# main_board.net
KiCad netlist of a schematic drawn in EAGLE
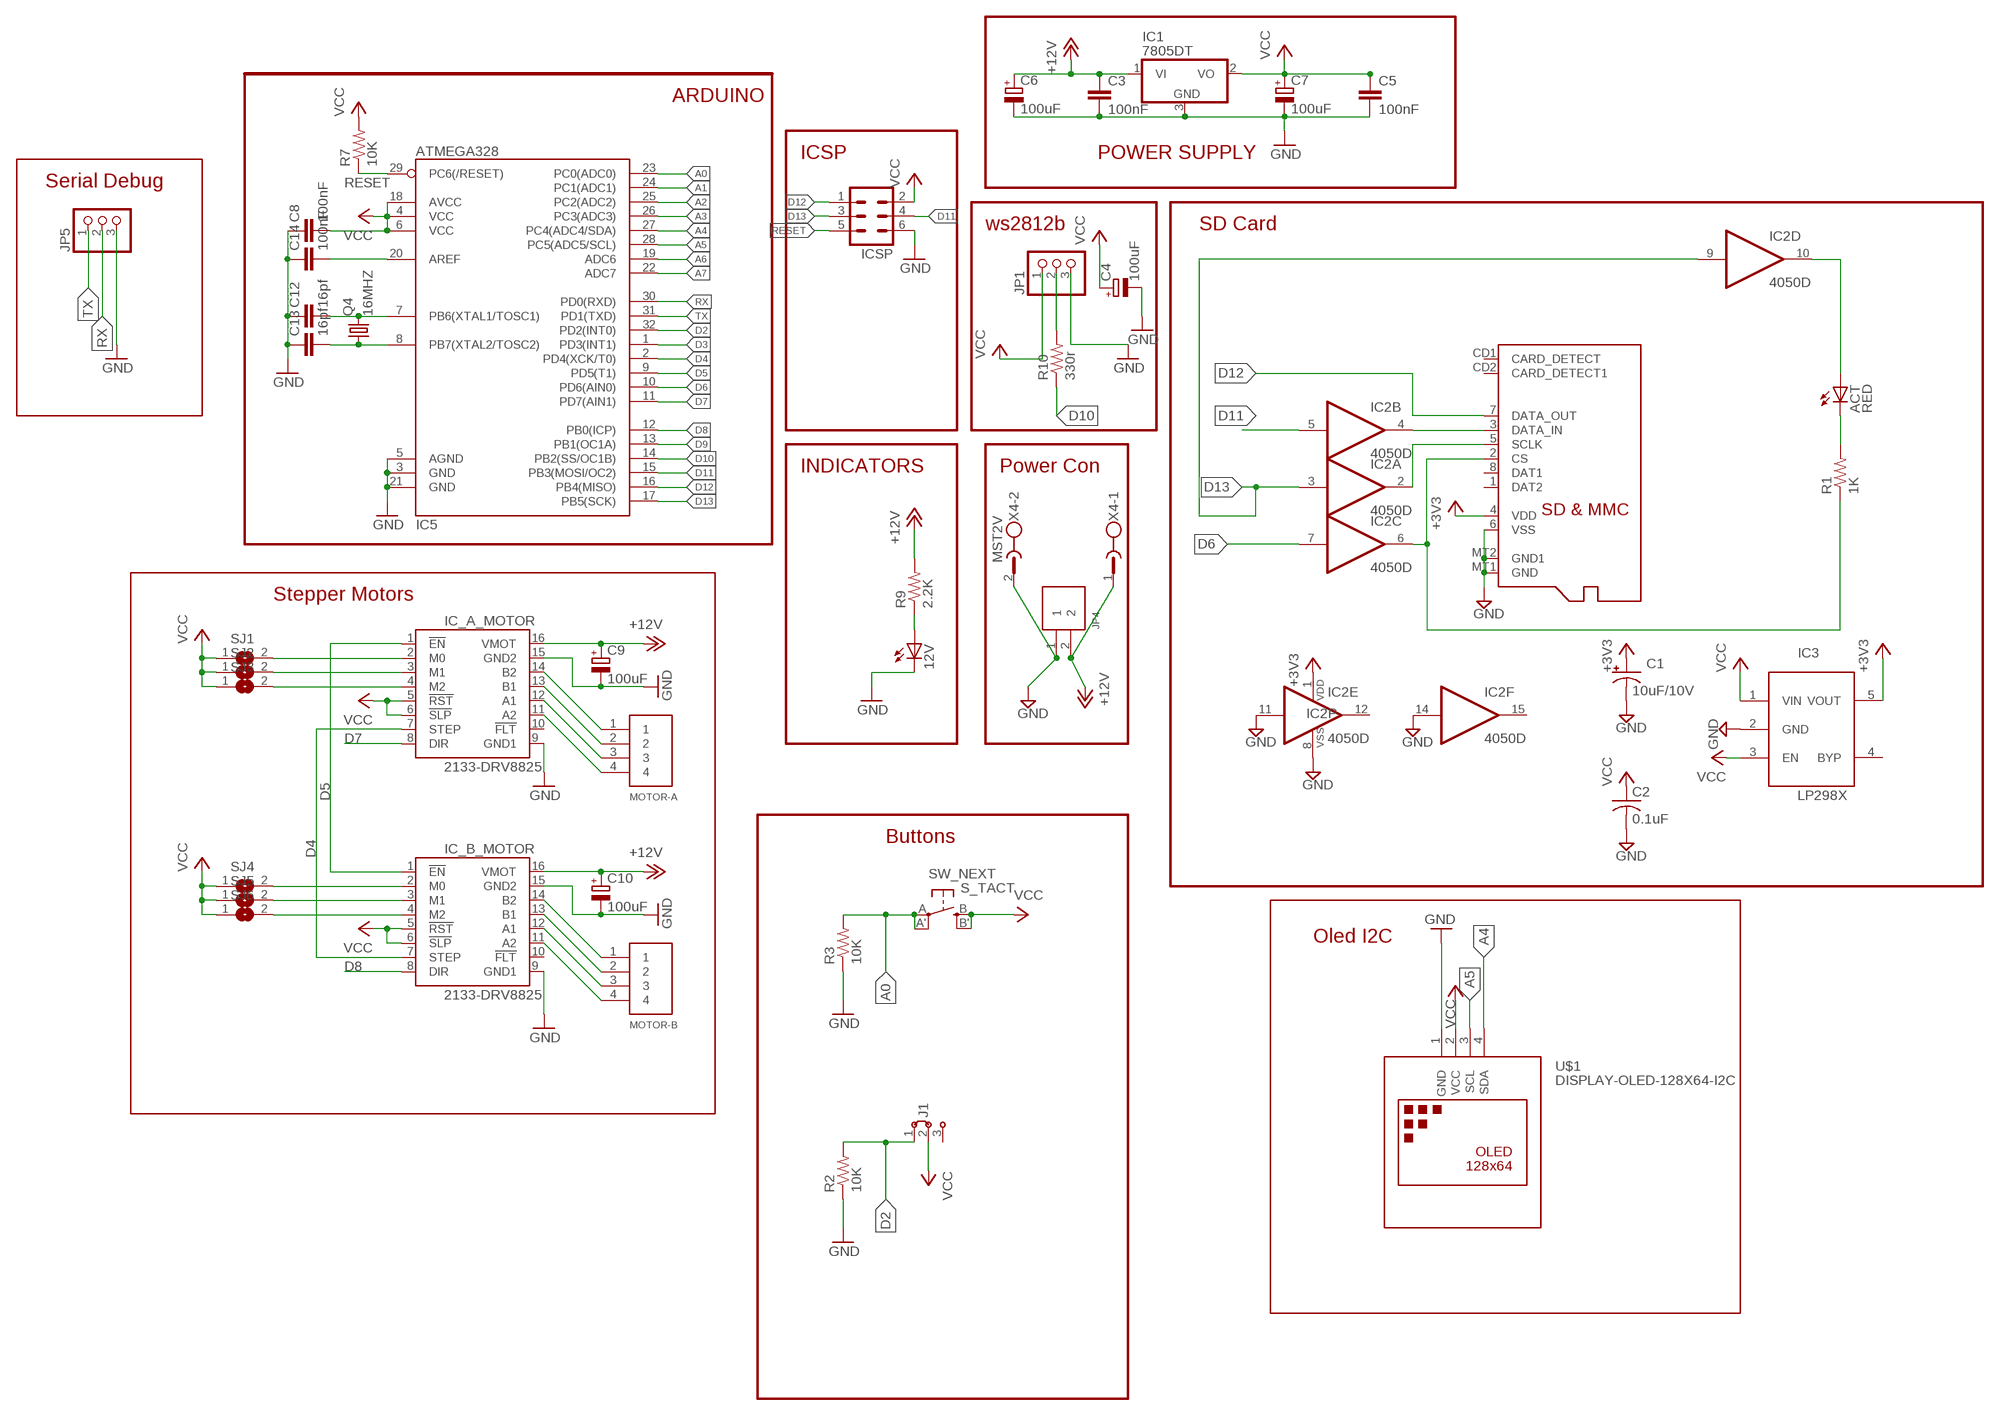
[diagram p0: schematic, sheet 1]

(export (version "E")
  (design (tool "Eeschema 10.0.6"))
  (components
    (comp (ref "12V")
      (value "LED0805")
      (footprint "eagle-import:LED-0805")
      (libsource (lib "eagle-import") (part "LED0805"))
    )
    (comp (ref "ACT")
      (value "RED")
      (footprint "eagle-import:CHIP-LED0805")
      (libsource (lib "eagle-import") (part "LEDCHIP-LED0805"))
    )
    (comp (ref "C1")
      (value "10uF/10V")
      (footprint "eagle-import:A_3216-18R")
      (libsource (lib "eagle-import") (part "CPOL-USA/3216-18R"))
    )
    (comp (ref "C2")
      (value "0.1uF")
      (footprint "eagle-import:C0805K")
      (libsource (lib "eagle-import") (part "C-USC0805K"))
    )
    (comp (ref "C3")
      (value "100nF")
      (footprint "eagle-import:0805")
      (libsource (lib "eagle-import") (part "CAP0805"))
    )
    (comp (ref "C4")
      (value "100uF")
      (footprint "eagle-import:E3,5-8")
      (libsource (lib "eagle-import") (part "CPOL-EUE3.5-8"))
    )
    (comp (ref "C5")
      (value "100nF")
      (footprint "eagle-import:0805")
      (libsource (lib "eagle-import") (part "CAP0805"))
    )
    (comp (ref "C6")
      (value "100uF")
      (footprint "eagle-import:E3,5-8")
      (libsource (lib "eagle-import") (part "CPOL-EUE3.5-8"))
    )
    (comp (ref "C7")
      (value "100uF")
      (footprint "eagle-import:E3,5-8")
      (libsource (lib "eagle-import") (part "CPOL-EUE3.5-8"))
    )
    (comp (ref "C8")
      (value "100nF")
      (footprint "eagle-import:0805")
      (libsource (lib "eagle-import") (part "CAP0805"))
    )
    (comp (ref "C9")
      (value "100uF")
      (footprint "eagle-import:E3,5-8")
      (libsource (lib "eagle-import") (part "CPOL-EUE3.5-8"))
    )
    (comp (ref "C10")
      (value "100uF")
      (footprint "eagle-import:E3,5-8")
      (libsource (lib "eagle-import") (part "CPOL-EUE3.5-8"))
    )
    (comp (ref "C12")
      (value "16pf")
      (footprint "eagle-import:0805")
      (libsource (lib "eagle-import") (part "CAP0805"))
    )
    (comp (ref "C13")
      (value "16pf")
      (footprint "eagle-import:0805")
      (libsource (lib "eagle-import") (part "CAP0805"))
    )
    (comp (ref "C14")
      (value "100nF")
      (footprint "eagle-import:0805")
      (libsource (lib "eagle-import") (part "CAP0805"))
    )
    (comp (ref "IC1")
      (value "7805DT")
      (footprint "eagle-import:TO252")
      (libsource (lib "eagle-import") (part "78DT05"))
    )
    (comp (ref "IC2")
      (value "4050D")
      (footprint "eagle-import:SO16")
      (libsource (lib "eagle-import") (part "4050D"))
    )
    (comp (ref "IC3")
      (value "LP298XS")
      (footprint "eagle-import:SOT23-5L")
      (libsource (lib "eagle-import") (part "LP298XS"))
    )
    (comp (ref "IC5")
      (value "ATMEGA328")
      (footprint "eagle-import:TQFP32-08")
      (libsource (lib "eagle-import") (part "ATMEGA168"))
    )
    (comp (ref "ICSP")
      (value "ML6")
      (footprint "eagle-import:ML6")
      (libsource (lib "eagle-import") (part "ML6"))
    )
    (comp (ref "IC_A_MOTOR")
      (value "2133-DRV8825")
      (footprint "eagle-import:DRV8825")
      (libsource (lib "eagle-import") (part "2133-DRV8825"))
    )
    (comp (ref "IC_B_MOTOR")
      (value "2133-DRV8825")
      (footprint "eagle-import:DRV8825")
      (libsource (lib "eagle-import") (part "2133-DRV8825"))
    )
    (comp (ref "J1")
      (value "J2X5MM")
      (footprint "eagle-import:05C")
      (libsource (lib "eagle-import") (part "J2X5MM"))
    )
    (comp (ref "JP1")
      (value "PINHD-1X3")
      (footprint "eagle-import:1X03")
      (libsource (lib "eagle-import") (part "PINHD-1X3"))
    )
    (comp (ref "JP4")
      (value "2PIN")
      (footprint "eagle-import:B2B-PH-K-S")
      (libsource (lib "eagle-import") (part "2PIN"))
    )
    (comp (ref "JP5")
      (value "PINHD-1X3")
      (footprint "eagle-import:1X03")
      (libsource (lib "eagle-import") (part "PINHD-1X3"))
    )
    (comp (ref "MOTOR-A")
      (value "4PIN")
      (footprint "eagle-import:B4B-PH-K-S")
      (libsource (lib "eagle-import") (part "4PIN"))
    )
    (comp (ref "MOTOR-B")
      (value "4PIN")
      (footprint "eagle-import:B4B-PH-K-S")
      (libsource (lib "eagle-import") (part "4PIN"))
    )
    (comp (ref "Q4")
      (value "16MHZ")
      (footprint "eagle-import:HC49_S")
      (libsource (lib "eagle-import") (part "CRYSTALHC49S"))
    )
    (comp (ref "R1")
      (value "1K")
      (footprint "eagle-import:R0805")
      (libsource (lib "eagle-import") (part "R-US_R0805"))
    )
    (comp (ref "R2")
      (value "10K")
      (footprint "eagle-import:R0805")
      (libsource (lib "eagle-import") (part "R-US_R0805"))
    )
    (comp (ref "R3")
      (value "10K")
      (footprint "eagle-import:R0805")
      (libsource (lib "eagle-import") (part "R-US_R0805"))
    )
    (comp (ref "R7")
      (value "10K")
      (footprint "eagle-import:0805")
      (libsource (lib "eagle-import") (part "RESISTOR"))
    )
    (comp (ref "R9")
      (value "2.2K")
      (footprint "eagle-import:0805")
      (libsource (lib "eagle-import") (part "RESISTOR"))
    )
    (comp (ref "R10")
      (value "330r")
      (footprint "eagle-import:R0805")
      (libsource (lib "eagle-import") (part "R-US_R0805"))
    )
    (comp (ref "SJ1") (value "SJ") (footprint "eagle-import:SJ") (libsource (lib "eagle-import") (part "SJ")))
    (comp (ref "SJ2") (value "SJ") (footprint "eagle-import:SJ") (libsource (lib "eagle-import") (part "SJ")))
    (comp (ref "SJ3") (value "SJ") (footprint "eagle-import:SJ") (libsource (lib "eagle-import") (part "SJ")))
    (comp (ref "SJ4") (value "SJ") (footprint "eagle-import:SJ") (libsource (lib "eagle-import") (part "SJ")))
    (comp (ref "SJ5") (value "SJ") (footprint "eagle-import:SJ") (libsource (lib "eagle-import") (part "SJ")))
    (comp (ref "SJ6") (value "SJ") (footprint "eagle-import:SJ") (libsource (lib "eagle-import") (part "SJ")))
    (comp (ref "SW_NEXT")
      (value "S_TACT")
      (footprint "eagle-import:EVQ-Q2")
      (libsource (lib "eagle-import") (part "SPST_TACT-EVQQ2"))
    )
    (comp (ref "U$1")
      (value "DISPLAY-OLED-128X64-I2C")
      (footprint "eagle-import:DISPLAY-OLED-128X64-I2C")
      (libsource (lib "eagle-import") (part "DISPLAY-OLED-128X64-I2C"))
    )
    (comp (ref "X1")
      (value "MICROSD")
      (footprint "eagle-import:MICROSD")
      (libsource (lib "eagle-import") (part "MICROSD"))
    )
    (comp (ref "X4")
      (value "MST2V")
      (footprint "eagle-import:MSTBV2")
      (libsource (lib "eagle-import") (part "MST2V"))
    )
  )
  (nets
    (net (code "1") (name "+3V3") (class "Default")
      (node (ref "C1") (pin "+") (pinfunction "+_+") (pintype "passive"))
      (node (ref "IC2") (pin "1") (pinfunction "VDD_1") (pintype "power_in"))
      (node (ref "IC3") (pin "5") (pinfunction "VOUT_5") (pintype "bidirectional"))
      (node (ref "X1") (pin "4") (pinfunction "VDD_4") (pintype "power_in"))
    )
    (net (code "2") (name "+12V") (class "Default")
      (node (ref "C10") (pin "+") (pinfunction "+_+") (pintype "passive"))
      (node (ref "C3") (pin "1") (pinfunction "1_1") (pintype "passive"))
      (node (ref "C6") (pin "+") (pinfunction "+_+") (pintype "passive"))
      (node (ref "C9") (pin "+") (pinfunction "+_+") (pintype "passive"))
      (node (ref "IC1") (pin "1") (pinfunction "VI_1") (pintype "input"))
      (node (ref "IC_A_MOTOR") (pin "16") (pinfunction "VMOT_16") (pintype "power_in"))
      (node (ref "IC_B_MOTOR") (pin "16") (pinfunction "VMOT_16") (pintype "power_in"))
      (node (ref "JP4") (pin "2") (pinfunction "2_2") (pintype "bidirectional"))
      (node (ref "R9") (pin "2") (pinfunction "2_2") (pintype "passive"))
      (node (ref "X4") (pin "1") (pinfunction "1_1") (pintype "passive"))
    )
    (net (code "3") (name "A0") (class "Default")
      (node (ref "IC5") (pin "23") (pinfunction "PC0(ADC0)_23") (pintype "bidirectional"))
      (node (ref "R3") (pin "2") (pinfunction "2_2") (pintype "passive"))
      (node (ref "SW_NEXT") (pin "A") (pinfunction "P_A") (pintype "passive"))
      (node (ref "SW_NEXT") (pin "A'") (pinfunction "P1_A'") (pintype "passive"))
    )
    (net (code "4") (name "A1") (class "Default")
      (node (ref "IC5") (pin "24") (pinfunction "PC1(ADC1)_24") (pintype "bidirectional"))
    )
    (net (code "5") (name "A2") (class "Default")
      (node (ref "IC5") (pin "25") (pinfunction "PC2(ADC2)_25") (pintype "bidirectional"))
    )
    (net (code "6") (name "A3") (class "Default")
      (node (ref "IC5") (pin "26") (pinfunction "PC3(ADC3)_26") (pintype "bidirectional"))
    )
    (net (code "7") (name "A4") (class "Default")
      (node (ref "IC5") (pin "27") (pinfunction "PC4(ADC4/SDA)_27") (pintype "bidirectional"))
      (node (ref "U$1") (pin "4") (pinfunction "SDA_4") (pintype "bidirectional"))
    )
    (net (code "8") (name "A5") (class "Default")
      (node (ref "IC5") (pin "28") (pinfunction "PC5(ADC5/SCL)_28") (pintype "bidirectional"))
      (node (ref "U$1") (pin "3") (pinfunction "SCL_3") (pintype "bidirectional"))
    )
    (net (code "9") (name "A6") (class "Default")
      (node (ref "IC5") (pin "19") (pinfunction "ADC6_19") (pintype "bidirectional"))
    )
    (net (code "10") (name "A7") (class "Default")
      (node (ref "IC5") (pin "22") (pinfunction "ADC7_22") (pintype "bidirectional"))
    )
    (net (code "11") (name "D2") (class "Default")
      (node (ref "IC5") (pin "32") (pinfunction "PD2(INT0)_32") (pintype "bidirectional"))
      (node (ref "J1") (pin "1") (pinfunction "1_1") (pintype "passive"))
      (node (ref "R2") (pin "2") (pinfunction "2_2") (pintype "passive"))
    )
    (net (code "12") (name "D3") (class "Default")
      (node (ref "IC5") (pin "1") (pinfunction "PD3(INT1)_1") (pintype "bidirectional"))
    )
    (net (code "13") (name "D4") (class "Default")
      (node (ref "IC5") (pin "2") (pinfunction "PD4(XCK/T0)_2") (pintype "bidirectional"))
      (node (ref "IC_A_MOTOR") (pin "7") (pinfunction "STEP_7") (pintype "input"))
      (node (ref "IC_B_MOTOR") (pin "7") (pinfunction "STEP_7") (pintype "input"))
    )
    (net (code "14") (name "D5") (class "Default")
      (node (ref "IC5") (pin "9") (pinfunction "PD5(T1)_9") (pintype "bidirectional"))
      (node (ref "IC_A_MOTOR") (pin "1") (pinfunction "~{EN}_1") (pintype "passive"))
      (node (ref "IC_B_MOTOR") (pin "1") (pinfunction "~{EN}_1") (pintype "passive"))
    )
    (net (code "15") (name "D6") (class "Default")
      (node (ref "IC2") (pin "7") (pinfunction "I_7") (pintype "input"))
      (node (ref "IC5") (pin "10") (pinfunction "PD6(AIN0)_10") (pintype "bidirectional"))
    )
    (net (code "16") (name "D7") (class "Default")
      (node (ref "IC5") (pin "11") (pinfunction "PD7(AIN1)_11") (pintype "bidirectional"))
      (node (ref "IC_A_MOTOR") (pin "8") (pinfunction "DIR_8") (pintype "input"))
    )
    (net (code "17") (name "D8") (class "Default")
      (node (ref "IC5") (pin "12") (pinfunction "PB0(ICP)_12") (pintype "bidirectional"))
      (node (ref "IC_B_MOTOR") (pin "8") (pinfunction "DIR_8") (pintype "input"))
    )
    (net (code "18") (name "D9") (class "Default")
      (node (ref "IC5") (pin "13") (pinfunction "PB1(OC1A)_13") (pintype "bidirectional"))
    )
    (net (code "19") (name "D10") (class "Default")
      (node (ref "IC5") (pin "14") (pinfunction "PB2(SS/OC1B)_14") (pintype "bidirectional"))
      (node (ref "R10") (pin "1") (pinfunction "1_1") (pintype "passive"))
    )
    (net (code "20") (name "D11") (class "Default")
      (node (ref "IC2") (pin "5") (pinfunction "I_5") (pintype "input"))
      (node (ref "IC5") (pin "15") (pinfunction "PB3(MOSI/OC2)_15") (pintype "bidirectional"))
      (node (ref "ICSP") (pin "4") (pinfunction "4_4") (pintype "passive"))
    )
    (net (code "21") (name "D12") (class "Default")
      (node (ref "IC5") (pin "16") (pinfunction "PB4(MISO)_16") (pintype "bidirectional"))
      (node (ref "ICSP") (pin "1") (pinfunction "1_1") (pintype "passive"))
      (node (ref "X1") (pin "7") (pinfunction "DATA_OUT_7") (pintype "output"))
    )
    (net (code "22") (name "D13") (class "Default")
      (node (ref "IC2") (pin "3") (pinfunction "I_3") (pintype "input"))
      (node (ref "IC2") (pin "9") (pinfunction "I_9") (pintype "input"))
      (node (ref "IC5") (pin "17") (pinfunction "PB5(SCK)_17") (pintype "bidirectional"))
      (node (ref "ICSP") (pin "3") (pinfunction "3_3") (pintype "passive"))
    )
    (net (code "23") (name "GND") (class "Default")
      (node (ref "12V") (pin "C") (pinfunction "C_C") (pintype "passive"))
      (node (ref "C1") (pin "-") (pinfunction "-_-") (pintype "passive"))
      (node (ref "C10") (pin "-") (pinfunction "-_-") (pintype "passive"))
      (node (ref "C12") (pin "1") (pinfunction "1_1") (pintype "passive"))
      (node (ref "C13") (pin "1") (pinfunction "1_1") (pintype "passive"))
      (node (ref "C14") (pin "1") (pinfunction "1_1") (pintype "passive"))
      (node (ref "C2") (pin "2") (pinfunction "2_2") (pintype "passive"))
      (node (ref "C3") (pin "2") (pinfunction "2_2") (pintype "passive"))
      (node (ref "C4") (pin "-") (pinfunction "-_-") (pintype "passive"))
      (node (ref "C5") (pin "2") (pinfunction "2_2") (pintype "passive"))
      (node (ref "C6") (pin "-") (pinfunction "-_-") (pintype "passive"))
      (node (ref "C7") (pin "-") (pinfunction "-_-") (pintype "passive"))
      (node (ref "C8") (pin "1") (pinfunction "1_1") (pintype "passive"))
      (node (ref "C9") (pin "-") (pinfunction "-_-") (pintype "passive"))
      (node (ref "IC1") (pin "3") (pinfunction "GND_3") (pintype "passive"))
      (node (ref "IC2") (pin "11") (pinfunction "I_11") (pintype "input"))
      (node (ref "IC2") (pin "14") (pinfunction "I_14") (pintype "input"))
      (node (ref "IC2") (pin "8") (pinfunction "VSS_8") (pintype "power_in"))
      (node (ref "IC3") (pin "2") (pinfunction "GND_2") (pintype "bidirectional"))
      (node (ref "IC5") (pin "21") (pinfunction "GND_21") (pintype "bidirectional"))
      (node (ref "IC5") (pin "3") (pinfunction "GND_3") (pintype "bidirectional"))
      (node (ref "IC5") (pin "5") (pinfunction "AGND_5") (pintype "bidirectional"))
      (node (ref "ICSP") (pin "6") (pinfunction "6_6") (pintype "passive"))
      (node (ref "IC_A_MOTOR") (pin "15") (pinfunction "GND2_15") (pintype "power_in"))
      (node (ref "IC_A_MOTOR") (pin "9") (pinfunction "GND1_9") (pintype "power_in"))
      (node (ref "IC_B_MOTOR") (pin "15") (pinfunction "GND2_15") (pintype "power_in"))
      (node (ref "IC_B_MOTOR") (pin "9") (pinfunction "GND1_9") (pintype "power_in"))
      (node (ref "JP1") (pin "3") (pinfunction "3_3") (pintype "passive"))
      (node (ref "JP4") (pin "1") (pinfunction "1_1") (pintype "bidirectional"))
      (node (ref "JP5") (pin "3") (pinfunction "3_3") (pintype "passive"))
      (node (ref "R2") (pin "1") (pinfunction "1_1") (pintype "passive"))
      (node (ref "R3") (pin "1") (pinfunction "1_1") (pintype "passive"))
      (node (ref "U$1") (pin "1") (pinfunction "GND_1") (pintype "power_in"))
      (node (ref "X1") (pin "6") (pinfunction "VSS_6") (pintype "power_in"))
      (node (ref "X1") (pin "MT1") (pinfunction "GND_MT1") (pintype "power_in"))
      (node (ref "X1") (pin "MT2") (pinfunction "GND1_MT2") (pintype "power_in"))
      (node (ref "X4") (pin "2") (pinfunction "1_2") (pintype "passive"))
    )
    (net (code "24") (name "Net-(12V-PadA)") (class "Default")
      (node (ref "12V") (pin "A") (pinfunction "A_A") (pintype "passive"))
      (node (ref "R9") (pin "1") (pinfunction "1_1") (pintype "passive"))
    )
    (net (code "25") (name "Net-(ACT-PadC)") (class "Default")
      (node (ref "ACT") (pin "C") (pinfunction "C_C") (pintype "passive"))
      (node (ref "R1") (pin "2") (pinfunction "2_2") (pintype "passive"))
    )
    (net (code "26") (name "Net-(IC2A-O)") (class "Default")
      (node (ref "IC2") (pin "2") (pinfunction "O_2") (pintype "output"))
      (node (ref "X1") (pin "5") (pinfunction "SCLK_5") (pintype "input"))
    )
    (net (code "27") (name "Net-(IC2B-O)") (class "Default")
      (node (ref "IC2") (pin "4") (pinfunction "O_4") (pintype "output"))
      (node (ref "X1") (pin "3") (pinfunction "DATA_IN_3") (pintype "input"))
    )
    (net (code "28") (name "Net-(IC2C-O)") (class "Default")
      (node (ref "IC2") (pin "6") (pinfunction "O_6") (pintype "output"))
      (node (ref "R1") (pin "1") (pinfunction "1_1") (pintype "passive"))
      (node (ref "X1") (pin "2") (pinfunction "CS_2") (pintype "input"))
    )
    (net (code "29") (name "Net-(IC2D-O)") (class "Default")
      (node (ref "ACT") (pin "A") (pinfunction "A_A") (pintype "passive"))
      (node (ref "IC2") (pin "10") (pinfunction "O_10") (pintype "output"))
    )
    (net (code "30") (name "Net-(IC5-AREF)") (class "Default")
      (node (ref "C14") (pin "2") (pinfunction "2_2") (pintype "passive"))
      (node (ref "IC5") (pin "20") (pinfunction "AREF_20") (pintype "bidirectional"))
    )
    (net (code "31") (name "Net-(IC5-PB6(XTAL1{slash}TOSC1))") (class "Default")
      (node (ref "C12") (pin "2") (pinfunction "2_2") (pintype "passive"))
      (node (ref "IC5") (pin "7") (pinfunction "PB6(XTAL1/TOSC1)_7") (pintype "bidirectional"))
      (node (ref "Q4") (pin "2") (pinfunction "2_2") (pintype "passive"))
    )
    (net (code "32") (name "Net-(IC5-PB7(XTAL2{slash}TOSC2))") (class "Default")
      (node (ref "C13") (pin "2") (pinfunction "2_2") (pintype "passive"))
      (node (ref "IC5") (pin "8") (pinfunction "PB7(XTAL2/TOSC2)_8") (pintype "bidirectional"))
      (node (ref "Q4") (pin "1") (pinfunction "1_1") (pintype "passive"))
    )
    (net (code "33") (name "Net-(IC_A_MOTOR-A1)") (class "Default")
      (node (ref "IC_A_MOTOR") (pin "12") (pinfunction "A1_12") (pintype "output"))
      (node (ref "MOTOR-A") (pin "3") (pinfunction "3_3") (pintype "bidirectional"))
    )
    (net (code "34") (name "Net-(IC_A_MOTOR-A2)") (class "Default")
      (node (ref "IC_A_MOTOR") (pin "11") (pinfunction "A2_11") (pintype "output"))
      (node (ref "MOTOR-A") (pin "4") (pinfunction "4_4") (pintype "bidirectional"))
    )
    (net (code "35") (name "Net-(IC_A_MOTOR-B1)") (class "Default")
      (node (ref "IC_A_MOTOR") (pin "13") (pinfunction "B1_13") (pintype "output"))
      (node (ref "MOTOR-A") (pin "2") (pinfunction "2_2") (pintype "bidirectional"))
    )
    (net (code "36") (name "Net-(IC_A_MOTOR-B2)") (class "Default")
      (node (ref "IC_A_MOTOR") (pin "14") (pinfunction "B2_14") (pintype "output"))
      (node (ref "MOTOR-A") (pin "1") (pinfunction "1_1") (pintype "bidirectional"))
    )
    (net (code "37") (name "Net-(IC_A_MOTOR-M0)") (class "Default")
      (node (ref "IC_A_MOTOR") (pin "2") (pinfunction "M0_2") (pintype "passive"))
      (node (ref "SJ1") (pin "2") (pinfunction "2_2") (pintype "passive"))
    )
    (net (code "38") (name "Net-(IC_A_MOTOR-M1)") (class "Default")
      (node (ref "IC_A_MOTOR") (pin "3") (pinfunction "M1_3") (pintype "passive"))
      (node (ref "SJ2") (pin "2") (pinfunction "2_2") (pintype "passive"))
    )
    (net (code "39") (name "Net-(IC_A_MOTOR-M2)") (class "Default")
      (node (ref "IC_A_MOTOR") (pin "4") (pinfunction "M2_4") (pintype "passive"))
      (node (ref "SJ3") (pin "2") (pinfunction "2_2") (pintype "passive"))
    )
    (net (code "40") (name "Net-(IC_B_MOTOR-A1)") (class "Default")
      (node (ref "IC_B_MOTOR") (pin "12") (pinfunction "A1_12") (pintype "output"))
      (node (ref "MOTOR-B") (pin "3") (pinfunction "3_3") (pintype "bidirectional"))
    )
    (net (code "41") (name "Net-(IC_B_MOTOR-A2)") (class "Default")
      (node (ref "IC_B_MOTOR") (pin "11") (pinfunction "A2_11") (pintype "output"))
      (node (ref "MOTOR-B") (pin "4") (pinfunction "4_4") (pintype "bidirectional"))
    )
    (net (code "42") (name "Net-(IC_B_MOTOR-B1)") (class "Default")
      (node (ref "IC_B_MOTOR") (pin "13") (pinfunction "B1_13") (pintype "output"))
      (node (ref "MOTOR-B") (pin "2") (pinfunction "2_2") (pintype "bidirectional"))
    )
    (net (code "43") (name "Net-(IC_B_MOTOR-B2)") (class "Default")
      (node (ref "IC_B_MOTOR") (pin "14") (pinfunction "B2_14") (pintype "output"))
      (node (ref "MOTOR-B") (pin "1") (pinfunction "1_1") (pintype "bidirectional"))
    )
    (net (code "44") (name "Net-(IC_B_MOTOR-M0)") (class "Default")
      (node (ref "IC_B_MOTOR") (pin "2") (pinfunction "M0_2") (pintype "passive"))
      (node (ref "SJ4") (pin "2") (pinfunction "2_2") (pintype "passive"))
    )
    (net (code "45") (name "Net-(IC_B_MOTOR-M1)") (class "Default")
      (node (ref "IC_B_MOTOR") (pin "3") (pinfunction "M1_3") (pintype "passive"))
      (node (ref "SJ5") (pin "2") (pinfunction "2_2") (pintype "passive"))
    )
    (net (code "46") (name "Net-(IC_B_MOTOR-M2)") (class "Default")
      (node (ref "IC_B_MOTOR") (pin "4") (pinfunction "M2_4") (pintype "passive"))
      (node (ref "SJ6") (pin "2") (pinfunction "2_2") (pintype "passive"))
    )
    (net (code "47") (name "Net-(JP1-Pad2)") (class "Default")
      (node (ref "JP1") (pin "2") (pinfunction "2_2") (pintype "passive"))
      (node (ref "R10") (pin "2") (pinfunction "2_2") (pintype "passive"))
    )
    (net (code "48") (name "RESET") (class "Default")
      (node (ref "IC5") (pin "29") (pinfunction "PC6(/RESET)_29") (pintype "bidirectional"))
      (node (ref "ICSP") (pin "5") (pinfunction "5_5") (pintype "passive"))
      (node (ref "R7") (pin "1") (pinfunction "1_1") (pintype "passive"))
    )
    (net (code "49") (name "RX") (class "Default")
      (node (ref "IC5") (pin "30") (pinfunction "PD0(RXD)_30") (pintype "bidirectional"))
      (node (ref "JP5") (pin "2") (pinfunction "2_2") (pintype "passive"))
    )
    (net (code "50") (name "TX") (class "Default")
      (node (ref "IC5") (pin "31") (pinfunction "PD1(TXD)_31") (pintype "bidirectional"))
      (node (ref "JP5") (pin "1") (pinfunction "1_1") (pintype "passive"))
    )
    (net (code "51") (name "VCC") (class "Default")
      (node (ref "C2") (pin "1") (pinfunction "1_1") (pintype "passive"))
      (node (ref "C4") (pin "+") (pinfunction "+_+") (pintype "passive"))
      (node (ref "C5") (pin "1") (pinfunction "1_1") (pintype "passive"))
      (node (ref "C7") (pin "+") (pinfunction "+_+") (pintype "passive"))
      (node (ref "C8") (pin "2") (pinfunction "2_2") (pintype "passive"))
      (node (ref "IC1") (pin "2") (pinfunction "VO_2") (pintype "passive"))
      (node (ref "IC3") (pin "1") (pinfunction "VIN_1") (pintype "bidirectional"))
      (node (ref "IC3") (pin "3") (pinfunction "EN_3") (pintype "bidirectional"))
      (node (ref "IC5") (pin "18") (pinfunction "AVCC_18") (pintype "bidirectional"))
      (node (ref "IC5") (pin "4") (pinfunction "VCC_4") (pintype "bidirectional"))
      (node (ref "IC5") (pin "6") (pinfunction "VCC_6") (pintype "bidirectional"))
      (node (ref "ICSP") (pin "2") (pinfunction "2_2") (pintype "passive"))
      (node (ref "IC_A_MOTOR") (pin "5") (pinfunction "~{RST}_5") (pintype "input"))
      (node (ref "IC_A_MOTOR") (pin "6") (pinfunction "~{SLP}_6") (pintype "input"))
      (node (ref "IC_B_MOTOR") (pin "5") (pinfunction "~{RST}_5") (pintype "input"))
      (node (ref "IC_B_MOTOR") (pin "6") (pinfunction "~{SLP}_6") (pintype "input"))
      (node (ref "J1") (pin "2") (pinfunction "2_2") (pintype "passive"))
      (node (ref "JP1") (pin "1") (pinfunction "1_1") (pintype "passive"))
      (node (ref "R7") (pin "2") (pinfunction "2_2") (pintype "passive"))
      (node (ref "SJ1") (pin "1") (pinfunction "1_1") (pintype "passive"))
      (node (ref "SJ2") (pin "1") (pinfunction "1_1") (pintype "passive"))
      (node (ref "SJ3") (pin "1") (pinfunction "1_1") (pintype "passive"))
      (node (ref "SJ4") (pin "1") (pinfunction "1_1") (pintype "passive"))
      (node (ref "SJ5") (pin "1") (pinfunction "1_1") (pintype "passive"))
      (node (ref "SJ6") (pin "1") (pinfunction "1_1") (pintype "passive"))
      (node (ref "SW_NEXT") (pin "B") (pinfunction "S_B") (pintype "passive"))
      (node (ref "SW_NEXT") (pin "B'") (pinfunction "S1_B'") (pintype "passive"))
      (node (ref "U$1") (pin "2") (pinfunction "VCC_2") (pintype "power_in"))
    )
    (net (code "52") (name "unconnected-(IC2E-O-Pad12)") (class "Default")
      (node (ref "IC2") (pin "12") (pinfunction "O_12") (pintype "output"))
    )
    (net (code "53") (name "unconnected-(IC2F-O-Pad15)") (class "Default")
      (node (ref "IC2") (pin "15") (pinfunction "O_15") (pintype "output"))
    )
    (net (code "54") (name "unconnected-(IC3-BYP-Pad4)") (class "Default")
      (node (ref "IC3") (pin "4") (pinfunction "BYP_4") (pintype "bidirectional"))
    )
    (net (code "55") (name "unconnected-(IC_A_MOTOR-~{FLT}-Pad10)") (class "Default")
      (node (ref "IC_A_MOTOR") (pin "10") (pinfunction "~{FLT}_10") (pintype "open_collector"))
    )
    (net (code "56") (name "unconnected-(IC_B_MOTOR-~{FLT}-Pad10)") (class "Default")
      (node (ref "IC_B_MOTOR") (pin "10") (pinfunction "~{FLT}_10") (pintype "open_collector"))
    )
    (net (code "57") (name "unconnected-(J1-Pad3)") (class "Default")
      (node (ref "J1") (pin "3") (pinfunction "3_3") (pintype "passive"))
    )
    (net (code "58") (name "unconnected-(X1-CARD_DETECT-PadCD1)") (class "Default")
      (node (ref "X1") (pin "CD1") (pinfunction "CARD_DETECT_CD1") (pintype "passive"))
    )
    (net (code "59") (name "unconnected-(X1-CARD_DETECT1-PadCD2)") (class "Default")
      (node (ref "X1") (pin "CD2") (pinfunction "CARD_DETECT1_CD2") (pintype "passive"))
    )
    (net (code "60") (name "unconnected-(X1-DAT1-Pad8)") (class "Default")
      (node (ref "X1") (pin "8") (pinfunction "DAT1_8") (pintype "bidirectional"))
    )
    (net (code "61") (name "unconnected-(X1-DAT2-Pad1)") (class "Default")
      (node (ref "X1") (pin "1") (pinfunction "DAT2_1") (pintype "bidirectional"))
    )
  )
)
